# AnalogConnector.net
KiCad netlist of a schematic drawn in Altium Designer
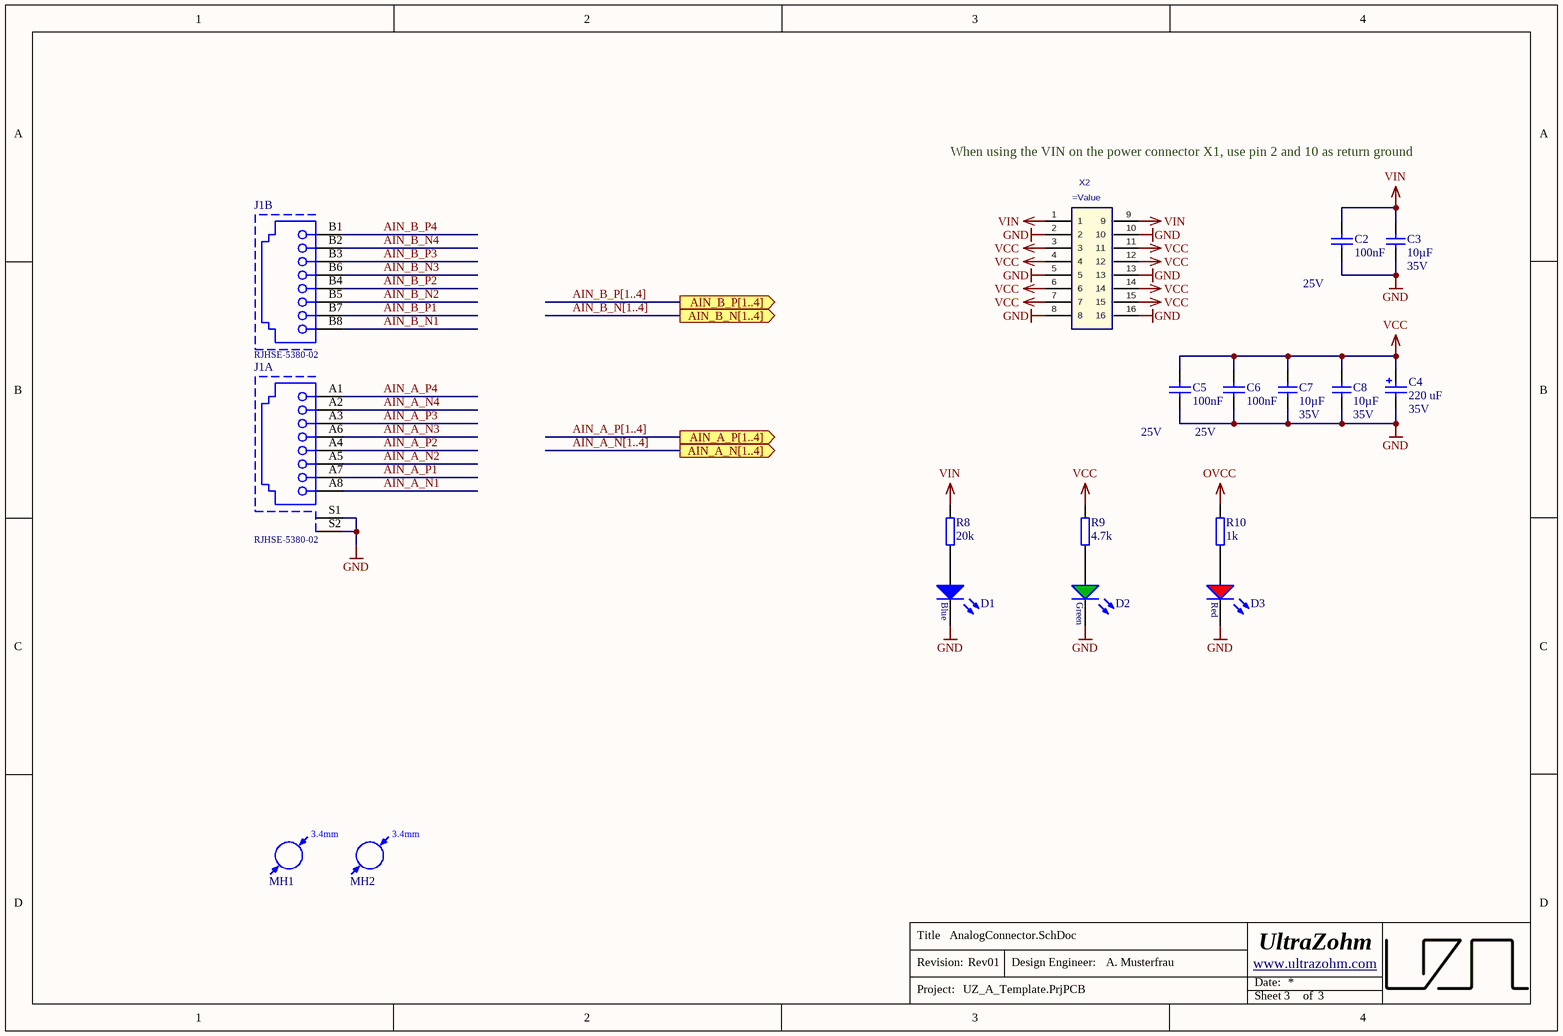
[diagram p0: AnalogConnector.SchDoc]

(export (version "E")
  (design (tool "Eeschema 10.0.6"))
  (components
    (comp (ref "C2")
      (value "100nF")
      (footprint "CAPC1608X07N")
      (fields (field (name "MF") "Würth") (field (name "MPN") "885012206071") (field (name "VOLTAGE") "25V"))
      (libsource (lib "UltraZohm_ADC") (part "Cap_0603"))
    )
    (comp (ref "C3")
      (value "10µF")
      (footprint "C_1206")
      (description "Capacitor 1206")
      (fields
        (field (name "TOLERANCE") "10%")
        (field (name "MF") "Murata Electronics")
        (field (name "VOLTAGE") "35V")
        (field (name "CREATED") "2018_06_25_AGeiger")
      )
      (libsource (lib "UltraZohm_ADC") (part "C_1206"))
    )
    (comp (ref "C4")
      (value "220 uF")
      (footprint "WCAP-ATG5_8x11.5x3.5")
      (description "WCAP-ATG5 Aluminum Electrolytic Capacitors, 8x11.5mm, 35 Vdc, 220 uF")
      (fields
        (field (name "PART NUMBER") "860020574012")
        (field (name "MF") "Wurth Elektronik")
        (field (name "VOLTAGE") "35V")
      )
      (libsource (lib "UltraZohm_ADC") (part "860020574012"))
    )
    (comp (ref "C5")
      (value "100nF")
      (footprint "CAPC1608X07N")
      (fields (field (name "MF") "Würth") (field (name "MPN") "885012206071") (field (name "VOLTAGE") "25V"))
      (libsource (lib "UltraZohm_ADC") (part "Cap_0603"))
    )
    (comp (ref "C6")
      (value "100nF")
      (footprint "CAPC1608X07N")
      (fields (field (name "MF") "Würth") (field (name "MPN") "885012206071") (field (name "VOLTAGE") "25V"))
      (libsource (lib "UltraZohm_ADC") (part "Cap_0603"))
    )
    (comp (ref "C7")
      (value "10µF")
      (footprint "C_1206")
      (description "Capacitor 1206")
      (fields
        (field (name "TOLERANCE") "10%")
        (field (name "MF") "Murata Electronics")
        (field (name "VOLTAGE") "35V")
        (field (name "CREATED") "2018_06_25_AGeiger")
      )
      (libsource (lib "UltraZohm_ADC") (part "C_1206"))
    )
    (comp (ref "C8")
      (value "10µF")
      (footprint "C_1206")
      (description "Capacitor 1206")
      (fields
        (field (name "TOLERANCE") "10%")
        (field (name "MF") "Murata Electronics")
        (field (name "VOLTAGE") "35V")
        (field (name "CREATED") "2018_06_25_AGeiger")
      )
      (libsource (lib "UltraZohm_ADC") (part "C_1206"))
    )
    (comp (ref "D1")
      (value "150060BS75000")
      (footprint "WL-SMCW_0603")
      (description "WL-SMCW SMD Mono-color Chip LED Waterclear, size 0603, Blue, 3.2 V, 140°")
      (fields (field (name "MF") "Wuerth Elektronik") (field (name "CREATED") "2018_09_06_AGeiger"))
      (libsource (lib "UltraZohm_ADC") (part "LED_Blue_0603"))
    )
    (comp (ref "D2")
      (value "150060GS75000")
      (footprint "WL-SMCW_0603")
      (description "WL-SMCW SMD Mono-color Chip LED Waterclear, size 0603, Green, 3.2 V, 140°")
      (fields (field (name "MF") "Wuerth Elektronik") (field (name "CREATED") "2018_09_06_AGeiger"))
      (libsource (lib "UltraZohm_ADC") (part "LED_Green_0603"))
    )
    (comp (ref "D3")
      (value "150060RS75000")
      (footprint "WL-SMCW_0603")
      (description "WL-SMCW SMD Mono-color Chip LED Waterclear, size 0603, Red, 2 V, 140°")
      (fields (field (name "MF") "Wuerth Elektronik") (field (name "CREATED") "2018_09_06_AGeiger"))
      (libsource (lib "UltraZohm_ADC") (part "LED_Red_0603"))
    )
    (comp (ref "J1")
      (value "RJHSE-5380-02")
      (footprint "RJHSE-5380-02")
      (description "Modular Jack WR-MJ, Tab Up, Shielded, Dual Port, Righ Angle, THT, 8P8C")
      (fields (field (name "MF") "Amphenol"))
      (libsource (lib "UltraZohm_ADC") (part "RJHSE-5380-02"))
    )
    (comp (ref "MH1")
      (value "mounting hole 3,4mm")
      (footprint "MH_3.4")
      (description "Non plated through hole, 3.4mm")
      (libsource (lib "UltraZohm_ADC") (part "Mounting Hole"))
    )
    (comp (ref "MH2")
      (value "mounting hole 3,4mm")
      (footprint "MH_3.4")
      (description "Non plated through hole, 3.4mm")
      (libsource (lib "UltraZohm_ADC") (part "Mounting Hole"))
    )
    (comp (ref "R8")
      (value "20k")
      (footprint "RESC1608X06N")
      (fields (field (name "MF") "Vishay / Dale") (field (name "MPN") "CRCW060320K0JNEAC"))
      (libsource (lib "UltraZohm_ADC") (part "R_0603"))
    )
    (comp (ref "R9")
      (value "4.7k")
      (footprint "RESC1608X06N")
      (fields (field (name "MF") "Vishay / Dale") (field (name "MPN") "CRCW06034K70JNEAC"))
      (libsource (lib "UltraZohm_ADC") (part "R_0603"))
    )
    (comp (ref "R10")
      (value "1k")
      (footprint "RESC1608X06N")
      (fields (field (name "MF") "Vishay / Dale") (field (name "MPN") "CRCW06031K00JNEAC"))
      (libsource (lib "UltraZohm_ADC") (part "R_0603"))
    )
    (comp (ref "X2")
      (value "~")
      (footprint "IPL1-108-01-L-D-RA-K")
      (description "2.54mm Double Row Terminal Assembly")
      (fields (field (name "MF") "SAMTEC") (field (name "CREATED") "2018_09_17_AGeiger"))
      (libsource (lib "UltraZohm_ADC") (part "IPL1-108-XX-X-D-X"))
    )
  )
  (nets
    (net (code "1") (name "/AIN_A_N1") (class "Default")
      (node (ref "J1") (pin "A8") (pinfunction "A8_A8") (pintype "passive"))
    )
    (net (code "2") (name "/AIN_A_N2") (class "Default")
      (node (ref "J1") (pin "A5") (pinfunction "A5_A5") (pintype "passive"))
    )
    (net (code "3") (name "/AIN_A_N3") (class "Default")
      (node (ref "J1") (pin "A6") (pinfunction "A6_A6") (pintype "passive"))
    )
    (net (code "4") (name "/AIN_A_N4") (class "Default")
      (node (ref "J1") (pin "A2") (pinfunction "A2_A2") (pintype "passive"))
    )
    (net (code "6") (name "/AIN_A_P1") (class "Default")
      (node (ref "J1") (pin "A7") (pinfunction "A7_A7") (pintype "passive"))
    )
    (net (code "7") (name "/AIN_A_P2") (class "Default")
      (node (ref "J1") (pin "A4") (pinfunction "A4_A4") (pintype "passive"))
    )
    (net (code "8") (name "/AIN_A_P3") (class "Default")
      (node (ref "J1") (pin "A3") (pinfunction "A3_A3") (pintype "passive"))
    )
    (net (code "9") (name "/AIN_A_P4") (class "Default")
      (node (ref "J1") (pin "A1") (pinfunction "A1_A1") (pintype "passive"))
    )
    (net (code "11") (name "/AIN_B_N1") (class "Default")
      (node (ref "J1") (pin "B8") (pinfunction "B8_B8") (pintype "passive"))
    )
    (net (code "12") (name "/AIN_B_N2") (class "Default")
      (node (ref "J1") (pin "B5") (pinfunction "B5_B5") (pintype "passive"))
    )
    (net (code "13") (name "/AIN_B_N3") (class "Default")
      (node (ref "J1") (pin "B6") (pinfunction "B6_B6") (pintype "passive"))
    )
    (net (code "14") (name "/AIN_B_N4") (class "Default")
      (node (ref "J1") (pin "B2") (pinfunction "B2_B2") (pintype "passive"))
    )
    (net (code "16") (name "/AIN_B_P1") (class "Default")
      (node (ref "J1") (pin "B7") (pinfunction "B7_B7") (pintype "passive"))
    )
    (net (code "17") (name "/AIN_B_P2") (class "Default")
      (node (ref "J1") (pin "B4") (pinfunction "B4_B4") (pintype "passive"))
    )
    (net (code "18") (name "/AIN_B_P3") (class "Default")
      (node (ref "J1") (pin "B3") (pinfunction "B3_B3") (pintype "passive"))
    )
    (net (code "19") (name "/AIN_B_P4") (class "Default")
      (node (ref "J1") (pin "B1") (pinfunction "B1_B1") (pintype "passive"))
    )
    (net (code "21") (name "GND") (class "Default")
      (node (ref "C2") (pin "1") (pinfunction "1_1") (pintype "passive"))
      (node (ref "C3") (pin "1") (pinfunction "1_1") (pintype "passive"))
      (node (ref "C4") (pin "2") (pinfunction "N_2") (pintype "passive"))
      (node (ref "C5") (pin "1") (pinfunction "1_1") (pintype "passive"))
      (node (ref "C6") (pin "1") (pinfunction "1_1") (pintype "passive"))
      (node (ref "C7") (pin "1") (pinfunction "1_1") (pintype "passive"))
      (node (ref "C8") (pin "1") (pinfunction "1_1") (pintype "passive"))
      (node (ref "D1") (pin "1") (pinfunction "K_1") (pintype "passive"))
      (node (ref "D2") (pin "1") (pinfunction "K_1") (pintype "passive"))
      (node (ref "D3") (pin "1") (pinfunction "K_1") (pintype "passive"))
      (node (ref "J1") (pin "S1") (pinfunction "S1_S1") (pintype "passive"))
      (node (ref "J1") (pin "S2") (pinfunction "S2_S2") (pintype "passive"))
      (node (ref "X2") (pin "10") (pinfunction "10_10") (pintype "passive"))
      (node (ref "X2") (pin "13") (pinfunction "13_13") (pintype "passive"))
      (node (ref "X2") (pin "16") (pinfunction "16_16") (pintype "passive"))
      (node (ref "X2") (pin "2") (pinfunction "2_2") (pintype "passive"))
      (node (ref "X2") (pin "5") (pinfunction "5_5") (pintype "passive"))
      (node (ref "X2") (pin "8") (pinfunction "8_8") (pintype "passive"))
    )
    (net (code "22") (name "Net-(D1-A)") (class "Default")
      (node (ref "D1") (pin "2") (pinfunction "A_2") (pintype "passive"))
      (node (ref "R8") (pin "1") (pintype "passive"))
    )
    (net (code "23") (name "Net-(D2-A)") (class "Default")
      (node (ref "D2") (pin "2") (pinfunction "A_2") (pintype "passive"))
      (node (ref "R9") (pin "1") (pintype "passive"))
    )
    (net (code "24") (name "Net-(D3-A)") (class "Default")
      (node (ref "D3") (pin "2") (pinfunction "A_2") (pintype "passive"))
      (node (ref "R10") (pin "1") (pintype "passive"))
    )
    (net (code "25") (name "OVCC") (class "Default") (node (ref "R10") (pin "2") (pintype "passive")))
    (net (code "26") (name "VCC") (class "Default")
      (node (ref "C4") (pin "1") (pinfunction "P_1") (pintype "passive"))
      (node (ref "C5") (pin "2") (pinfunction "2_2") (pintype "passive"))
      (node (ref "C6") (pin "2") (pinfunction "2_2") (pintype "passive"))
      (node (ref "C7") (pin "2") (pinfunction "2_2") (pintype "passive"))
      (node (ref "C8") (pin "2") (pinfunction "2_2") (pintype "passive"))
      (node (ref "R9") (pin "2") (pintype "passive"))
      (node (ref "X2") (pin "11") (pinfunction "11_11") (pintype "passive"))
      (node (ref "X2") (pin "12") (pinfunction "12_12") (pintype "passive"))
      (node (ref "X2") (pin "14") (pinfunction "14_14") (pintype "passive"))
      (node (ref "X2") (pin "15") (pinfunction "15_15") (pintype "passive"))
      (node (ref "X2") (pin "3") (pinfunction "3_3") (pintype "passive"))
      (node (ref "X2") (pin "4") (pinfunction "4_4") (pintype "passive"))
      (node (ref "X2") (pin "6") (pinfunction "6_6") (pintype "passive"))
      (node (ref "X2") (pin "7") (pinfunction "7_7") (pintype "passive"))
    )
    (net (code "27") (name "VIN") (class "Default")
      (node (ref "C2") (pin "2") (pinfunction "2_2") (pintype "passive"))
      (node (ref "C3") (pin "2") (pinfunction "2_2") (pintype "passive"))
      (node (ref "R8") (pin "2") (pintype "passive"))
      (node (ref "X2") (pin "1") (pinfunction "1_1") (pintype "passive"))
      (node (ref "X2") (pin "9") (pinfunction "9_9") (pintype "passive"))
    )
  )
)
